# Sch_PowerSupply.net
KiCad netlist of a schematic drawn in EAGLE
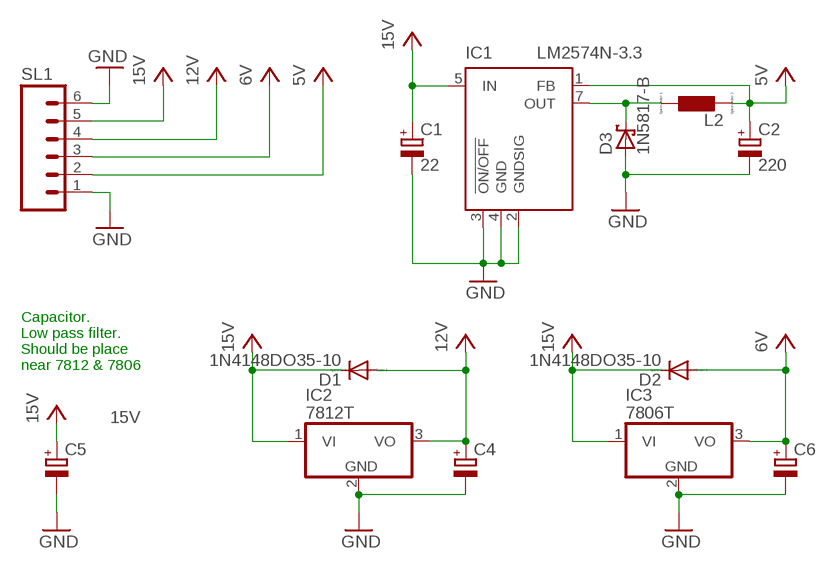
[diagram p0: schematic, sheet 1]

(export (version "E")
  (design (tool "Eeschema 10.0.6"))
  (components
    (comp (ref "C1")
      (value "22")
      (footprint "eagle-import:E5-8,5")
      (libsource (lib "eagle-import") (part "CPOL-EUE5-8.5"))
    )
    (comp (ref "C2")
      (value "220")
      (footprint "eagle-import:E5-8,5")
      (libsource (lib "eagle-import") (part "CPOL-EUE5-8.5"))
    )
    (comp (ref "C4")
      (value "CPOL-EUE5-8.5")
      (footprint "eagle-import:E5-8,5")
      (libsource (lib "eagle-import") (part "CPOL-EUE5-8.5"))
    )
    (comp (ref "C5")
      (value "CPOL-EUE5-8.5")
      (footprint "eagle-import:E5-8,5")
      (libsource (lib "eagle-import") (part "CPOL-EUE5-8.5"))
    )
    (comp (ref "C6")
      (value "CPOL-EUE5-8.5")
      (footprint "eagle-import:E5-8,5")
      (libsource (lib "eagle-import") (part "CPOL-EUE5-8.5"))
    )
    (comp (ref "D1")
      (value "1N4148DO35-10")
      (footprint "eagle-import:DO35-10")
      (libsource (lib "eagle-import") (part "1N4148DO35-10"))
    )
    (comp (ref "D2")
      (value "1N4148DO35-10")
      (footprint "eagle-import:DO35-10")
      (libsource (lib "eagle-import") (part "1N4148DO35-10"))
    )
    (comp (ref "D3")
      (value "1N5817-B")
      (footprint "eagle-import:DO41-7.6")
      (libsource (lib "eagle-import") (part "1N5817-B"))
    )
    (comp (ref "IC1")
      (value "LM2574N-3.3")
      (footprint "eagle-import:DIL08")
      (libsource (lib "eagle-import") (part "LM2574?-N3.3"))
    )
    (comp (ref "IC2")
      (value "7812T")
      (footprint "eagle-import:TO220H")
      (libsource (lib "eagle-import") (part "78T12"))
    )
    (comp (ref "IC3")
      (value "7806T")
      (footprint "eagle-import:TO220H")
      (libsource (lib "eagle-import") (part "78T06"))
    )
    (comp (ref "L2")
      (value "L0204/7")
      (footprint "eagle-import:0204_7")
      (libsource (lib "eagle-import") (part "L0204/7"))
    )
    (comp (ref "SL1")
      (value "M06")
      (footprint "eagle-import:06P")
      (libsource (lib "eagle-import") (part "M06"))
    )
  )
  (nets
    (net (code "1") (name "5V") (class "Default")
      (node (ref "C2") (pin "+") (pinfunction "+_+") (pintype "passive"))
      (node (ref "IC1") (pin "1") (pinfunction "FB_1") (pintype "input"))
      (node (ref "L2") (pin "2") (pinfunction "2_2") (pintype "passive"))
      (node (ref "SL1") (pin "2") (pinfunction "2_2") (pintype "passive"))
    )
    (net (code "2") (name "6V") (class "Default")
      (node (ref "C6") (pin "+") (pinfunction "+_+") (pintype "passive"))
      (node (ref "D2") (pin "A") (pinfunction "A_A") (pintype "passive"))
      (node (ref "IC3") (pin "3") (pinfunction "VO_3") (pintype "passive"))
      (node (ref "SL1") (pin "3") (pinfunction "3_3") (pintype "passive"))
    )
    (net (code "3") (name "12V") (class "Default")
      (node (ref "C4") (pin "+") (pinfunction "+_+") (pintype "passive"))
      (node (ref "D1") (pin "A") (pinfunction "A_A") (pintype "passive"))
      (node (ref "IC2") (pin "3") (pinfunction "VO_3") (pintype "passive"))
      (node (ref "SL1") (pin "4") (pinfunction "4_4") (pintype "passive"))
    )
    (net (code "4") (name "15V") (class "Default")
      (node (ref "C1") (pin "+") (pinfunction "+_+") (pintype "passive"))
      (node (ref "C5") (pin "+") (pinfunction "+_+") (pintype "passive"))
      (node (ref "D1") (pin "C") (pinfunction "C_C") (pintype "passive"))
      (node (ref "D2") (pin "C") (pinfunction "C_C") (pintype "passive"))
      (node (ref "IC1") (pin "5") (pinfunction "IN_5") (pintype "input"))
      (node (ref "IC2") (pin "1") (pinfunction "VI_1") (pintype "input"))
      (node (ref "IC3") (pin "1") (pinfunction "VI_1") (pintype "input"))
      (node (ref "SL1") (pin "5") (pinfunction "5_5") (pintype "passive"))
    )
    (net (code "5") (name "GND") (class "Default")
      (node (ref "C1") (pin "-") (pinfunction "-_-") (pintype "passive"))
      (node (ref "C2") (pin "-") (pinfunction "-_-") (pintype "passive"))
      (node (ref "C4") (pin "-") (pinfunction "-_-") (pintype "passive"))
      (node (ref "C5") (pin "-") (pinfunction "-_-") (pintype "passive"))
      (node (ref "C6") (pin "-") (pinfunction "-_-") (pintype "passive"))
      (node (ref "D3") (pin "A") (pinfunction "A_A") (pintype "passive"))
      (node (ref "IC1") (pin "2") (pinfunction "GNDSIG_2") (pintype "input"))
      (node (ref "IC1") (pin "3") (pinfunction "~{ON/OFF}_3") (pintype "input"))
      (node (ref "IC1") (pin "4") (pinfunction "GND_4") (pintype "power_in"))
      (node (ref "IC2") (pin "2") (pinfunction "GND_2") (pintype "passive"))
      (node (ref "IC3") (pin "2") (pinfunction "GND_2") (pintype "passive"))
      (node (ref "SL1") (pin "1") (pinfunction "1_1") (pintype "passive"))
      (node (ref "SL1") (pin "6") (pinfunction "6_6") (pintype "passive"))
    )
    (net (code "6") (name "Net-(IC1-OUT)") (class "Default")
      (node (ref "D3") (pin "C") (pinfunction "C_C") (pintype "passive"))
      (node (ref "IC1") (pin "7") (pinfunction "OUT_7") (pintype "passive"))
      (node (ref "L2") (pin "1") (pinfunction "1_1") (pintype "passive"))
    )
  )
)
